# Attenuator.net
KiCad netlist of a schematic drawn in Altium Designer
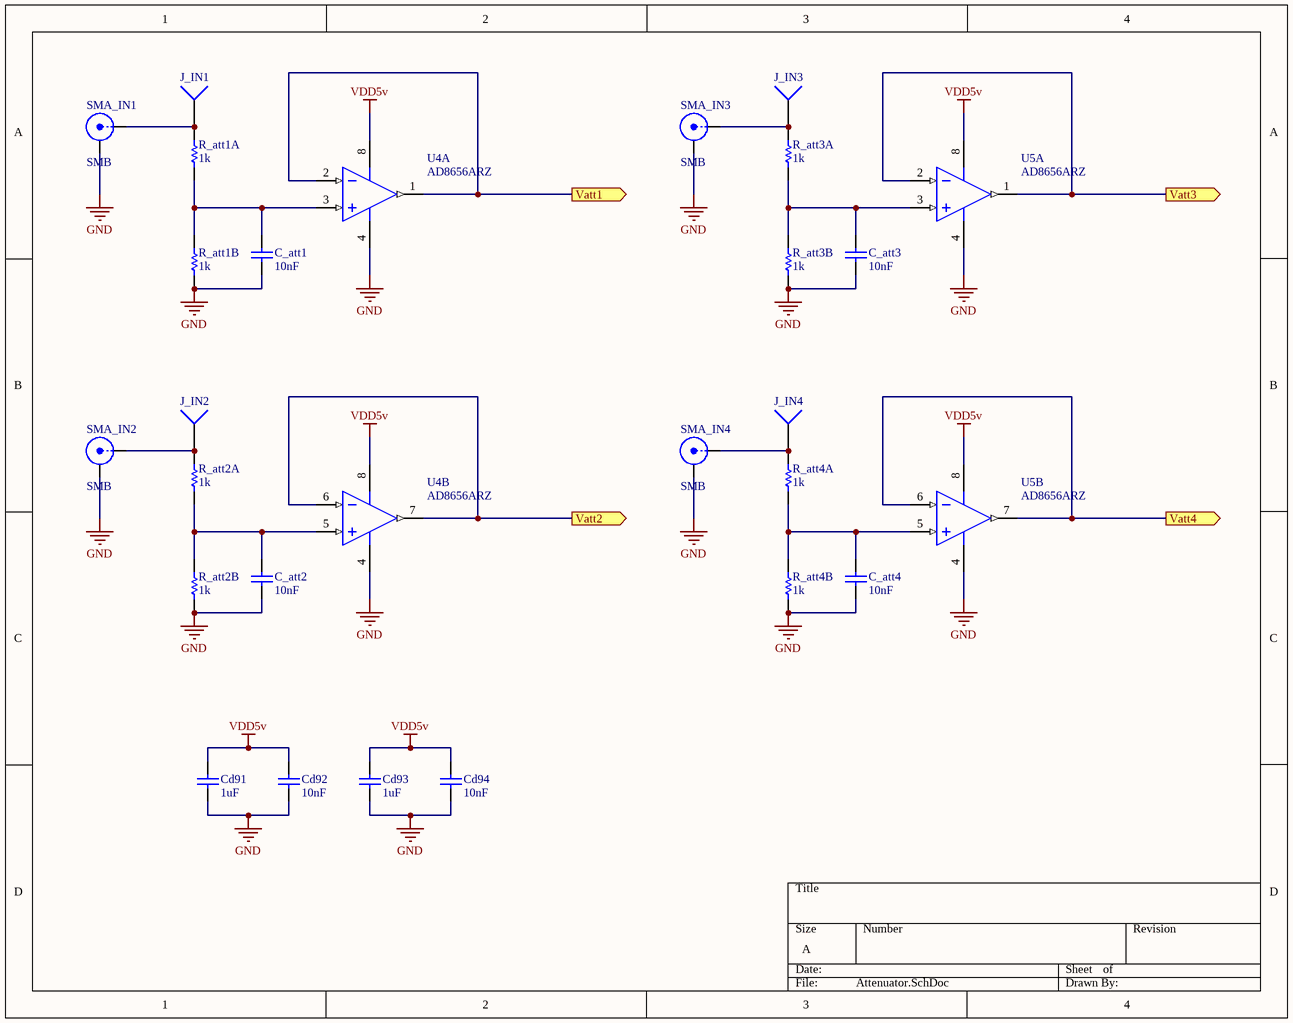
[diagram p0: Attenuator.SchDoc]

(export (version "E")
  (design (tool "Eeschema 10.0.6"))
  (components
    (comp (ref "Cd91")
      (value "1uF")
      (footprint "1608[0603]")
      (description "Capacitor")
      (fields (field (name "Comment") "Cap") (field (name "PUBLISHER") "Altium Limited"))
      (libsource (lib "Miscellaneous Devices") (part "Cap"))
    )
    (comp (ref "Cd92")
      (value "10nF")
      (footprint "1608[0603]")
      (description "Capacitor")
      (fields (field (name "Comment") "Cap") (field (name "PUBLISHER") "Altium Limited"))
      (libsource (lib "Miscellaneous Devices") (part "Cap"))
    )
    (comp (ref "Cd93")
      (value "1uF")
      (footprint "1608[0603]")
      (description "Capacitor")
      (fields (field (name "Comment") "Cap") (field (name "PUBLISHER") "Altium Limited"))
      (libsource (lib "Miscellaneous Devices") (part "Cap"))
    )
    (comp (ref "Cd94")
      (value "10nF")
      (footprint "1608[0603]")
      (description "Capacitor")
      (fields (field (name "Comment") "Cap") (field (name "PUBLISHER") "Altium Limited"))
      (libsource (lib "Miscellaneous Devices") (part "Cap"))
    )
    (comp (ref "C_att1")
      (value "10nF")
      (footprint "1608[0603]")
      (description "Capacitor")
      (fields (field (name "Comment") "Cap") (field (name "PUBLISHER") "Altium Limited"))
      (libsource (lib "Miscellaneous Devices") (part "Cap"))
    )
    (comp (ref "C_att2")
      (value "10nF")
      (footprint "1608[0603]")
      (description "Capacitor")
      (fields (field (name "Comment") "Cap") (field (name "PUBLISHER") "Altium Limited"))
      (libsource (lib "Miscellaneous Devices") (part "Cap"))
    )
    (comp (ref "C_att3")
      (value "10nF")
      (footprint "1608[0603]")
      (description "Capacitor")
      (fields (field (name "Comment") "Cap") (field (name "PUBLISHER") "Altium Limited"))
      (libsource (lib "Miscellaneous Devices") (part "Cap"))
    )
    (comp (ref "C_att4")
      (value "10nF")
      (footprint "1608[0603]")
      (description "Capacitor")
      (fields (field (name "Comment") "Cap") (field (name "PUBLISHER") "Altium Limited"))
      (libsource (lib "Miscellaneous Devices") (part "Cap"))
    )
    (comp (ref "J_IN1")
      (value "Socket")
      (footprint "PIN1")
      (fields (field (name "PUBLISHER") "Altium Limited"))
      (libsource (lib "Miscellaneous Connectors") (part "Socket"))
    )
    (comp (ref "J_IN2")
      (value "Socket")
      (footprint "PIN1")
      (fields (field (name "PUBLISHER") "Altium Limited"))
      (libsource (lib "Miscellaneous Connectors") (part "Socket"))
    )
    (comp (ref "J_IN3")
      (value "Socket")
      (footprint "PIN1")
      (fields (field (name "PUBLISHER") "Altium Limited"))
      (libsource (lib "Miscellaneous Connectors") (part "Socket"))
    )
    (comp (ref "J_IN4")
      (value "Socket")
      (footprint "PIN1")
      (fields (field (name "PUBLISHER") "Altium Limited"))
      (libsource (lib "Miscellaneous Connectors") (part "Socket"))
    )
    (comp (ref "R_att1A")
      (value "1k")
      (footprint "1608[0603]")
      (description "Resistor")
      (fields (field (name "Comment") "Res1") (field (name "PUBLISHER") "Altium Limited"))
      (libsource (lib "Miscellaneous Devices") (part "Res1"))
    )
    (comp (ref "R_att1B")
      (value "1k")
      (footprint "1608[0603]")
      (description "Resistor")
      (fields (field (name "Comment") "Res1") (field (name "PUBLISHER") "Altium Limited"))
      (libsource (lib "Miscellaneous Devices") (part "Res1"))
    )
    (comp (ref "R_att2A")
      (value "1k")
      (footprint "1608[0603]")
      (description "Resistor")
      (fields (field (name "Comment") "Res1") (field (name "PUBLISHER") "Altium Limited"))
      (libsource (lib "Miscellaneous Devices") (part "Res1"))
    )
    (comp (ref "R_att2B")
      (value "1k")
      (footprint "1608[0603]")
      (description "Resistor")
      (fields (field (name "Comment") "Res1") (field (name "PUBLISHER") "Altium Limited"))
      (libsource (lib "Miscellaneous Devices") (part "Res1"))
    )
    (comp (ref "R_att3A")
      (value "1k")
      (footprint "1608[0603]")
      (description "Resistor")
      (fields (field (name "Comment") "Res1") (field (name "PUBLISHER") "Altium Limited"))
      (libsource (lib "Miscellaneous Devices") (part "Res1"))
    )
    (comp (ref "R_att3B")
      (value "1k")
      (footprint "1608[0603]")
      (description "Resistor")
      (fields (field (name "Comment") "Res1") (field (name "PUBLISHER") "Altium Limited"))
      (libsource (lib "Miscellaneous Devices") (part "Res1"))
    )
    (comp (ref "R_att4A")
      (value "1k")
      (footprint "1608[0603]")
      (description "Resistor")
      (fields (field (name "Comment") "Res1") (field (name "PUBLISHER") "Altium Limited"))
      (libsource (lib "Miscellaneous Devices") (part "Res1"))
    )
    (comp (ref "R_att4B")
      (value "1k")
      (footprint "1608[0603]")
      (description "Resistor")
      (fields (field (name "Comment") "Res1") (field (name "PUBLISHER") "Altium Limited"))
      (libsource (lib "Miscellaneous Devices") (part "Res1"))
    )
    (comp (ref "SMA_IN1")
      (value "SMB")
      (footprint "SMB_V-RJ45")
      (description "SMB Straight Connector")
      (fields (field (name "PUBLISHER") "Altium Limited"))
      (libsource (lib "Miscellaneous Connectors") (part "SMB"))
    )
    (comp (ref "SMA_IN2")
      (value "SMB")
      (footprint "SMB_V-RJ45")
      (description "SMB Straight Connector")
      (fields (field (name "PUBLISHER") "Altium Limited"))
      (libsource (lib "Miscellaneous Connectors") (part "SMB"))
    )
    (comp (ref "SMA_IN3")
      (value "SMB")
      (footprint "SMB_V-RJ45")
      (description "SMB Straight Connector")
      (fields (field (name "PUBLISHER") "Altium Limited"))
      (libsource (lib "Miscellaneous Connectors") (part "SMB"))
    )
    (comp (ref "SMA_IN4")
      (value "SMB")
      (footprint "SMB_V-RJ45")
      (description "SMB Straight Connector")
      (fields (field (name "PUBLISHER") "Altium Limited"))
      (libsource (lib "Miscellaneous Connectors") (part "SMB"))
    )
    (comp (ref "U4")
      (value "AD8656ARZ")
      (footprint "ADI-R-8_N")
      (fields (field (name "GENERIC PART NUMBER") "AD8656") (field (name "MANUFACTURER") "Analog Devices"))
      (libsource (lib "Analog Devices Operational Amplifiers") (part "AD8656ARZ"))
    )
    (comp (ref "U5")
      (value "AD8656ARZ")
      (footprint "ADI-R-8_N")
      (fields (field (name "GENERIC PART NUMBER") "AD8656") (field (name "MANUFACTURER") "Analog Devices"))
      (libsource (lib "Analog Devices Operational Amplifiers") (part "AD8656ARZ"))
    )
  )
  (nets
    (net (code "1") (name "/Vatt1") (class "Default")
      (node (ref "U4") (pin "1") (pinfunction "OUT_A_1") (pintype "output"))
      (node (ref "U4") (pin "2") (pinfunction "-IN_A_2") (pintype "input"))
    )
    (net (code "2") (name "/Vatt2") (class "Default")
      (node (ref "U4") (pin "6") (pinfunction "-IN_B_6") (pintype "input"))
      (node (ref "U4") (pin "7") (pinfunction "OUT_B_7") (pintype "output"))
    )
    (net (code "3") (name "/Vatt3") (class "Default")
      (node (ref "U5") (pin "1") (pinfunction "OUT_A_1") (pintype "output"))
      (node (ref "U5") (pin "2") (pinfunction "-IN_A_2") (pintype "input"))
    )
    (net (code "4") (name "/Vatt4") (class "Default")
      (node (ref "U5") (pin "6") (pinfunction "-IN_B_6") (pintype "input"))
      (node (ref "U5") (pin "7") (pinfunction "OUT_B_7") (pintype "output"))
    )
    (net (code "5") (name "GND") (class "Default")
      (node (ref "C_att1") (pin "2") (pinfunction "2_2") (pintype "passive"))
      (node (ref "C_att2") (pin "2") (pinfunction "2_2") (pintype "passive"))
      (node (ref "C_att3") (pin "2") (pinfunction "2_2") (pintype "passive"))
      (node (ref "C_att4") (pin "2") (pinfunction "2_2") (pintype "passive"))
      (node (ref "Cd91") (pin "2") (pinfunction "2_2") (pintype "passive"))
      (node (ref "Cd92") (pin "2") (pinfunction "2_2") (pintype "passive"))
      (node (ref "Cd93") (pin "2") (pinfunction "2_2") (pintype "passive"))
      (node (ref "Cd94") (pin "2") (pinfunction "2_2") (pintype "passive"))
      (node (ref "R_att1B") (pin "1") (pinfunction "1_1") (pintype "passive"))
      (node (ref "R_att2B") (pin "1") (pinfunction "1_1") (pintype "passive"))
      (node (ref "R_att3B") (pin "1") (pinfunction "1_1") (pintype "passive"))
      (node (ref "R_att4B") (pin "1") (pinfunction "1_1") (pintype "passive"))
      (node (ref "SMA_IN1") (pin "2") (pinfunction "Y_2") (pintype "passive"))
      (node (ref "SMA_IN2") (pin "2") (pinfunction "Y_2") (pintype "passive"))
      (node (ref "SMA_IN3") (pin "2") (pinfunction "Y_2") (pintype "passive"))
      (node (ref "SMA_IN4") (pin "2") (pinfunction "Y_2") (pintype "passive"))
      (node (ref "U4") (pin "4") (pinfunction "-V_4") (pintype "power_in"))
      (node (ref "U5") (pin "4") (pinfunction "-V_4") (pintype "power_in"))
    )
    (net (code "6") (name "Net-(SMA_IN1-X)") (class "Default")
      (node (ref "J_IN1") (pin "1") (pinfunction "1_1") (pintype "passive"))
      (node (ref "R_att1A") (pin "2") (pinfunction "2_2") (pintype "passive"))
      (node (ref "SMA_IN1") (pin "1") (pinfunction "X_1") (pintype "passive"))
    )
    (net (code "7") (name "Net-(SMA_IN2-X)") (class "Default")
      (node (ref "J_IN2") (pin "1") (pinfunction "1_1") (pintype "passive"))
      (node (ref "R_att2A") (pin "2") (pinfunction "2_2") (pintype "passive"))
      (node (ref "SMA_IN2") (pin "1") (pinfunction "X_1") (pintype "passive"))
    )
    (net (code "8") (name "Net-(SMA_IN3-X)") (class "Default")
      (node (ref "J_IN3") (pin "1") (pinfunction "1_1") (pintype "passive"))
      (node (ref "R_att3A") (pin "2") (pinfunction "2_2") (pintype "passive"))
      (node (ref "SMA_IN3") (pin "1") (pinfunction "X_1") (pintype "passive"))
    )
    (net (code "9") (name "Net-(SMA_IN4-X)") (class "Default")
      (node (ref "J_IN4") (pin "1") (pinfunction "1_1") (pintype "passive"))
      (node (ref "R_att4A") (pin "2") (pinfunction "2_2") (pintype "passive"))
      (node (ref "SMA_IN4") (pin "1") (pinfunction "X_1") (pintype "passive"))
    )
    (net (code "10") (name "Net-(U4A-+IN_A)") (class "Default")
      (node (ref "C_att1") (pin "1") (pinfunction "1_1") (pintype "passive"))
      (node (ref "R_att1A") (pin "1") (pinfunction "1_1") (pintype "passive"))
      (node (ref "R_att1B") (pin "2") (pinfunction "2_2") (pintype "passive"))
      (node (ref "U4") (pin "3") (pinfunction "+IN_A_3") (pintype "input"))
    )
    (net (code "11") (name "Net-(U4B-+IN_B)") (class "Default")
      (node (ref "C_att2") (pin "1") (pinfunction "1_1") (pintype "passive"))
      (node (ref "R_att2A") (pin "1") (pinfunction "1_1") (pintype "passive"))
      (node (ref "R_att2B") (pin "2") (pinfunction "2_2") (pintype "passive"))
      (node (ref "U4") (pin "5") (pinfunction "+IN_B_5") (pintype "input"))
    )
    (net (code "12") (name "Net-(U5A-+IN_A)") (class "Default")
      (node (ref "C_att3") (pin "1") (pinfunction "1_1") (pintype "passive"))
      (node (ref "R_att3A") (pin "1") (pinfunction "1_1") (pintype "passive"))
      (node (ref "R_att3B") (pin "2") (pinfunction "2_2") (pintype "passive"))
      (node (ref "U5") (pin "3") (pinfunction "+IN_A_3") (pintype "input"))
    )
    (net (code "13") (name "Net-(U5B-+IN_B)") (class "Default")
      (node (ref "C_att4") (pin "1") (pinfunction "1_1") (pintype "passive"))
      (node (ref "R_att4A") (pin "1") (pinfunction "1_1") (pintype "passive"))
      (node (ref "R_att4B") (pin "2") (pinfunction "2_2") (pintype "passive"))
      (node (ref "U5") (pin "5") (pinfunction "+IN_B_5") (pintype "input"))
    )
    (net (code "14") (name "VDD5v") (class "Default")
      (node (ref "Cd91") (pin "1") (pinfunction "1_1") (pintype "passive"))
      (node (ref "Cd92") (pin "1") (pinfunction "1_1") (pintype "passive"))
      (node (ref "Cd93") (pin "1") (pinfunction "1_1") (pintype "passive"))
      (node (ref "Cd94") (pin "1") (pinfunction "1_1") (pintype "passive"))
      (node (ref "U4") (pin "8") (pinfunction "+V_8") (pintype "power_in"))
      (node (ref "U5") (pin "8") (pinfunction "+V_8") (pintype "power_in"))
    )
  )
)
